# 12_Raspbbery_CM3.net
KiCad netlist of a schematic drawn in Altium Designer
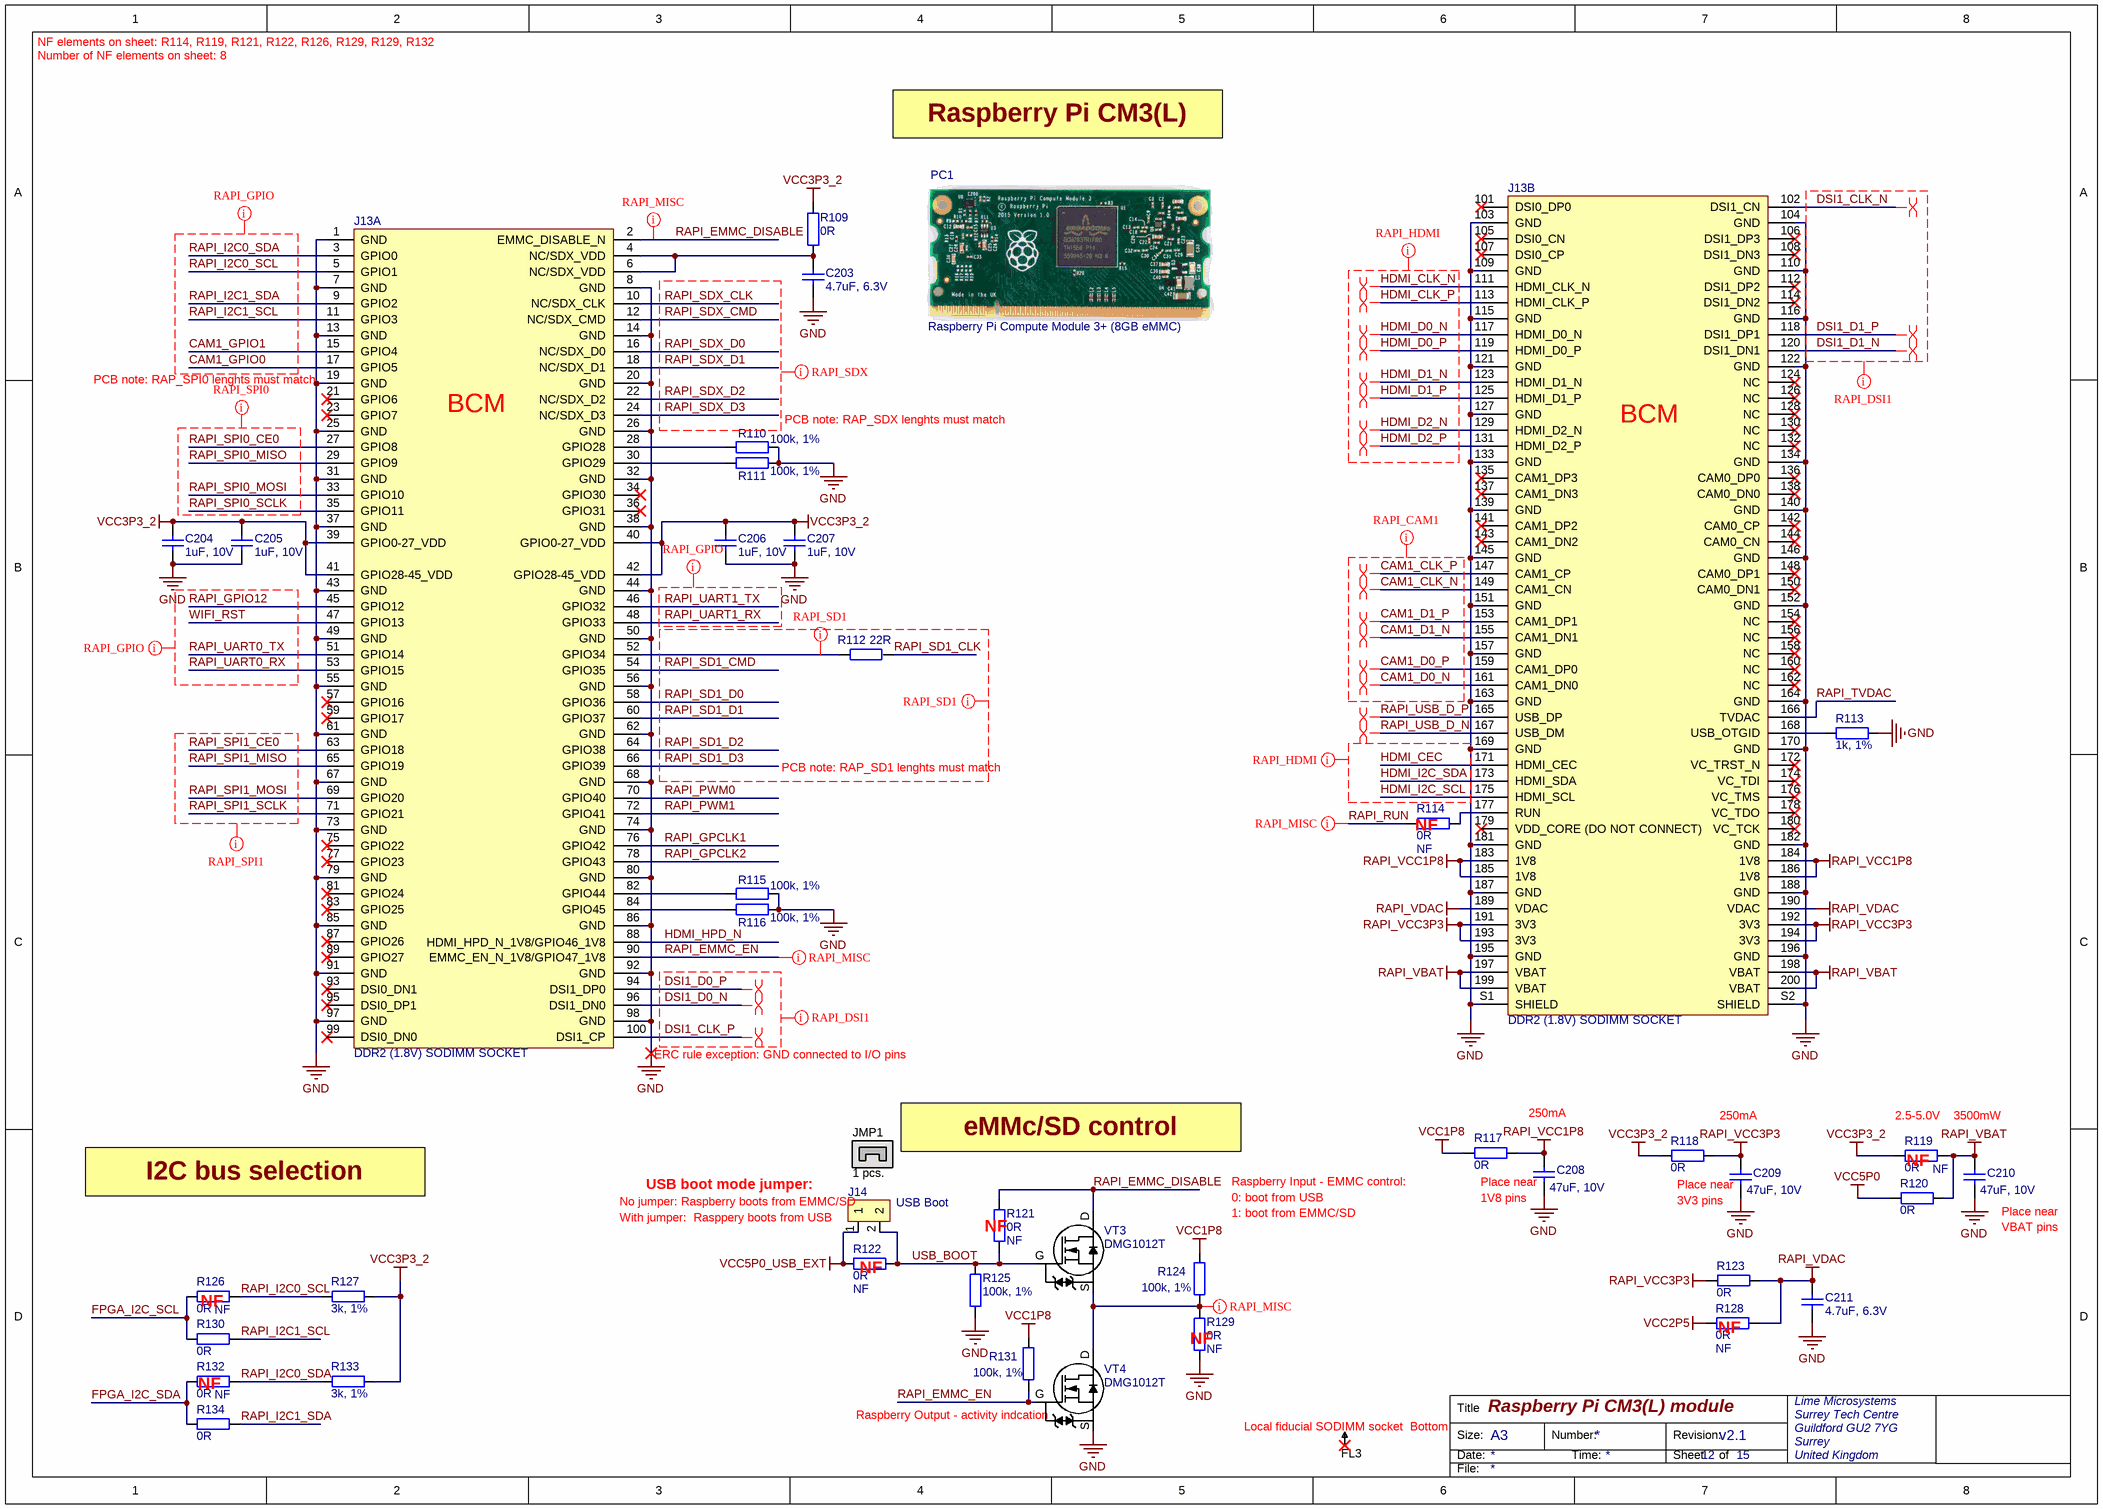
[diagram p0: 12_Raspbbery CM3.SchDoc]

(export (version "E")
  (design (tool "Eeschema 10.0.6"))
  (components
    (comp (ref "C203")
      (value "4.7uF, 6.3V")
      (footprint "CAP0402")
      (fields
        (field (name "MANUFACTURER") "Murata Electronics North America")
        (field (name "TOLERANCE") "±20%")
      )
      (libsource (lib "LimeMicroAltiumLib_schLib") (part "Cap_0402"))
    )
    (comp (ref "C204")
      (value "1uF, 10V")
      (footprint "CAP0402")
      (description "CAP CER 1UF 10V X5R 0402")
      (fields (field (name "MANUFACTURER") "Yageo") (field (name "TOLERANCE") "±20%"))
      (libsource (lib "LimeMicroAltiumLib_schLib") (part "Cap_0402"))
    )
    (comp (ref "C205")
      (value "1uF, 10V")
      (footprint "CAP0402")
      (description "CAP CER 1UF 10V X5R 0402")
      (fields (field (name "MANUFACTURER") "Yageo") (field (name "TOLERANCE") "±20%"))
      (libsource (lib "LimeMicroAltiumLib_schLib") (part "Cap_0402"))
    )
    (comp (ref "C206")
      (value "1uF, 10V")
      (footprint "CAP0402")
      (description "CAP CER 1UF 10V X5R 0402")
      (fields (field (name "MANUFACTURER") "Yageo") (field (name "TOLERANCE") "±20%"))
      (libsource (lib "LimeMicroAltiumLib_schLib") (part "Cap_0402"))
    )
    (comp (ref "C207")
      (value "1uF, 10V")
      (footprint "CAP0402")
      (description "CAP CER 1UF 10V X5R 0402")
      (fields (field (name "MANUFACTURER") "Yageo") (field (name "TOLERANCE") "±20%"))
      (libsource (lib "LimeMicroAltiumLib_schLib") (part "Cap_0402"))
    )
    (comp (ref "C208")
      (value "47uF, 10V")
      (footprint "CAP1206")
      (fields (field (name "TOLERANCE") "±20%") (field (name "MANUFACTURER") "TDK Corporation"))
      (libsource (lib "LimeFPGAboard_schLib") (part "Cap_1206"))
    )
    (comp (ref "C209")
      (value "47uF, 10V")
      (footprint "CAP1206")
      (fields (field (name "TOLERANCE") "±20%") (field (name "MANUFACTURER") "TDK Corporation"))
      (libsource (lib "LimeFPGAboard_schLib") (part "Cap_1206"))
    )
    (comp (ref "C210")
      (value "47uF, 10V")
      (footprint "CAP1206")
      (fields (field (name "TOLERANCE") "±20%") (field (name "MANUFACTURER") "TDK Corporation"))
      (libsource (lib "LimeFPGAboard_schLib") (part "Cap_1206"))
    )
    (comp (ref "C211")
      (value "4.7uF, 6.3V")
      (footprint "CAP0402")
      (fields
        (field (name "MANUFACTURER") "Murata Electronics North America")
        (field (name "TOLERANCE") "±20%")
      )
      (libsource (lib "LimeMicroAltiumLib_schLib") (part "Cap_0402"))
    )
    (comp (ref "FL3")
      (value "Fiducial")
      (footprint "Fiducial_local")
      (libsource (lib "VGTU_Altium_lib") (part "Fiducial"))
    )
    (comp (ref "J13")
      (value "DDR2 (1.8V) SODIMM SOCKET")
      (footprint "TE_1717254-1_DDR_SODIMM")
      (fields (field (name "MANUFACTURER") "TE Connectivity AMP Connectors"))
      (libsource (lib "LimeNet-Micro_2v1-SDR") (part "1717254-1"))
    )
    (comp (ref "J14")
      (value "USB Boot")
      (footprint "HDR_1x2")
      (fields (field (name "MANUFACTURER") "3M"))
      (libsource (lib "LimeFPGAboard_schLib") (part "Jumper"))
    )
    (comp (ref "JMP1")
      (value "1 pcs.")
      (description "Shorting Jumper, 2-position, 1.27mm pitch")
      (fields (field (name "MANUFACTURER") "Sullins"))
      (libsource (lib "LimeMicroAltiumLib_schLib") (part "JUMP_2P_CONN_HEADER"))
    )
    (comp (ref "PC1")
      (value "Raspberry Pi Compute Module 3+ (8GB eMMC)")
      (fields (field (name "MANUFACTURER") "RASPBERRY-PI"))
      (libsource (lib "LimeMicroAltiumLib_schLib_r01") (part "Raspberry_RPI-COMPUTE3"))
    )
    (comp (ref "R109")
      (value "0R")
      (footprint "RES0402")
      (fields (field (name "MANUFACTURER") "Yageo") (field (name "TOLERANCE") "Jumper"))
      (libsource (lib "LimeFPGAboard_schLib") (part "Res_0402"))
    )
    (comp (ref "R110")
      (value "100k, 1%")
      (footprint "RES0402")
      (fields
        (field (name "MANUFACTURER") "Vishay Dale")
        (field (name "TOLERANCE") "±1%")
        (field (name "MANUFACTURER PART NUMBER") "CRCW0402100KFKEDC")
      )
      (libsource (lib "LimeMicroAltiumLib_schLib") (part "Res_0402"))
    )
    (comp (ref "R111")
      (value "100k, 1%")
      (footprint "RES0402")
      (fields
        (field (name "MANUFACTURER") "Vishay Dale")
        (field (name "TOLERANCE") "±1%")
        (field (name "MANUFACTURER PART NUMBER") "CRCW0402100KFKEDC")
      )
      (libsource (lib "LimeMicroAltiumLib_schLib") (part "Res_0402"))
    )
    (comp (ref "R112")
      (value "22R")
      (footprint "RES0402")
      (fields (field (name "TOLERANCE") "±1%") (field (name "MANUFACTURER") "Yageo"))
      (libsource (lib "LimeFPGAboard_schLib") (part "Res_0402"))
    )
    (comp (ref "R113")
      (value "1k, 1%")
      (footprint "RES0402")
      (fields (field (name "MANUFACTURER") "Stackpole Electronics Inc") (field (name "TOLERANCE") "±1%"))
      (libsource (lib "LimeMicroAltiumLib_schLib") (part "Res_0402"))
    )
    (comp (ref "R114")
      (value "0R")
      (footprint "RES0402")
      (fields
        (field (name "MANUFACTURER") "Yageo")
        (field (name "ASSEMBLY INFO") "NF")
        (field (name "TOLERANCE") "Jumper")
      )
      (libsource (lib "LimeFPGAboard_schLib") (part "Res_0402"))
    )
    (comp (ref "R115")
      (value "100k, 1%")
      (footprint "RES0402")
      (fields
        (field (name "MANUFACTURER") "Vishay Dale")
        (field (name "TOLERANCE") "±1%")
        (field (name "MANUFACTURER PART NUMBER") "CRCW0402100KFKEDC")
      )
      (libsource (lib "LimeMicroAltiumLib_schLib") (part "Res_0402"))
    )
    (comp (ref "R116")
      (value "100k, 1%")
      (footprint "RES0402")
      (fields
        (field (name "MANUFACTURER") "Vishay Dale")
        (field (name "TOLERANCE") "±1%")
        (field (name "MANUFACTURER PART NUMBER") "CRCW0402100KFKEDC")
      )
      (libsource (lib "LimeMicroAltiumLib_schLib") (part "Res_0402"))
    )
    (comp (ref "R117")
      (value "0R")
      (footprint "RES0805")
      (fields (field (name "MANUFACTURER") "Vishay Dale") (field (name "TOLERANCE") "Jumper"))
      (libsource (lib "LimeMicroAltiumLib_schLib") (part "Res_0402"))
    )
    (comp (ref "R118")
      (value "0R")
      (footprint "RES0805")
      (fields (field (name "MANUFACTURER") "Vishay Dale") (field (name "TOLERANCE") "Jumper"))
      (libsource (lib "LimeMicroAltiumLib_schLib") (part "Res_0402"))
    )
    (comp (ref "R119")
      (value "0R")
      (footprint "RES0805")
      (fields
        (field (name "ASSEMBLY INFO") "NF")
        (field (name "MANUFACTURER") "Vishay Dale")
        (field (name "TOLERANCE") "Jumper")
      )
      (libsource (lib "LimeMicroAltiumLib_schLib") (part "Res_0402"))
    )
    (comp (ref "R120")
      (value "0R")
      (footprint "RES0805")
      (fields (field (name "MANUFACTURER") "Vishay Dale") (field (name "TOLERANCE") "Jumper"))
      (libsource (lib "LimeMicroAltiumLib_schLib") (part "Res_0402"))
    )
    (comp (ref "R121")
      (value "0R")
      (footprint "RES0402")
      (fields
        (field (name "MANUFACTURER") "Yageo")
        (field (name "ASSEMBLY INFO") "NF")
        (field (name "TOLERANCE") "Jumper")
      )
      (libsource (lib "LimeFPGAboard_schLib") (part "Res_0402"))
    )
    (comp (ref "R122")
      (value "0R")
      (footprint "RES0402")
      (fields
        (field (name "ASSEMBLY INFO") "NF")
        (field (name "MANUFACTURER") "Yageo")
        (field (name "TOLERANCE") "Jumper")
      )
      (libsource (lib "LimeMicroAltiumLib_schLib") (part "Res_0402"))
    )
    (comp (ref "R123")
      (value "0R")
      (footprint "RES0402")
      (fields (field (name "MANUFACTURER") "Yageo") (field (name "TOLERANCE") "Jumper"))
      (libsource (lib "LimeFPGAboard_schLib") (part "Res_0402"))
    )
    (comp (ref "R124")
      (value "100k, 1%")
      (footprint "RES0402")
      (fields
        (field (name "MANUFACTURER") "Vishay Dale")
        (field (name "TOLERANCE") "±1%")
        (field (name "MANUFACTURER PART NUMBER") "CRCW0402100KFKEDC")
      )
      (libsource (lib "LimeMicroAltiumLib_schLib") (part "Res_0402"))
    )
    (comp (ref "R125")
      (value "100k, 1%")
      (footprint "RES0402")
      (fields
        (field (name "MANUFACTURER") "Vishay Dale")
        (field (name "TOLERANCE") "±1%")
        (field (name "MANUFACTURER PART NUMBER") "CRCW0402100KFKEDC")
      )
      (libsource (lib "LimeMicroAltiumLib_schLib") (part "Res_0402"))
    )
    (comp (ref "R126")
      (value "0R")
      (footprint "RES0402")
      (fields
        (field (name "MANUFACTURER") "Yageo")
        (field (name "ASSEMBLY INFO") "NF")
        (field (name "TOLERANCE") "Jumper")
      )
      (libsource (lib "LimeFPGAboard_schLib") (part "Res_0402"))
    )
    (comp (ref "R127")
      (value "3k, 1%")
      (footprint "RES0402")
      (fields (field (name "TOLERANCE") "±1%") (field (name "MANUFACTURER") "Vishay Dale"))
      (libsource (lib "LimeMicroAltiumLib_schLib") (part "Res_0402"))
    )
    (comp (ref "R128")
      (value "0R")
      (footprint "RES0402")
      (fields
        (field (name "MANUFACTURER") "Yageo")
        (field (name "ASSEMBLY INFO") "NF")
        (field (name "TOLERANCE") "Jumper")
      )
      (libsource (lib "LimeFPGAboard_schLib") (part "Res_0402"))
    )
    (comp (ref "R129")
      (value "0R")
      (footprint "RES0402")
      (fields
        (field (name "MANUFACTURER") "Yageo")
        (field (name "ASSEMBLY INFO") "NF")
        (field (name "TOLERANCE") "Jumper")
      )
      (libsource (lib "LimeFPGAboard_schLib") (part "Res_0402"))
    )
    (comp (ref "R130")
      (value "0R")
      (footprint "RES0402")
      (fields (field (name "MANUFACTURER") "Yageo") (field (name "TOLERANCE") "Jumper"))
      (libsource (lib "LimeFPGAboard_schLib") (part "Res_0402"))
    )
    (comp (ref "R131")
      (value "100k, 1%")
      (footprint "RES0402")
      (fields
        (field (name "MANUFACTURER") "Vishay Dale")
        (field (name "TOLERANCE") "±1%")
        (field (name "MANUFACTURER PART NUMBER") "CRCW0402100KFKEDC")
      )
      (libsource (lib "LimeMicroAltiumLib_schLib") (part "Res_0402"))
    )
    (comp (ref "R132")
      (value "0R")
      (footprint "RES0402")
      (fields
        (field (name "MANUFACTURER") "Yageo")
        (field (name "ASSEMBLY INFO") "NF")
        (field (name "TOLERANCE") "Jumper")
      )
      (libsource (lib "LimeFPGAboard_schLib") (part "Res_0402"))
    )
    (comp (ref "R133")
      (value "3k, 1%")
      (footprint "RES0402")
      (fields (field (name "TOLERANCE") "±1%") (field (name "MANUFACTURER") "Vishay Dale"))
      (libsource (lib "LimeMicroAltiumLib_schLib") (part "Res_0402"))
    )
    (comp (ref "R134")
      (value "0R")
      (footprint "RES0402")
      (fields (field (name "MANUFACTURER") "Yageo") (field (name "TOLERANCE") "Jumper"))
      (libsource (lib "LimeFPGAboard_schLib") (part "Res_0402"))
    )
    (comp (ref "VT3")
      (value "DMG1012T")
      (footprint "SOT523")
      (fields (field (name "MANUFACTURER") "Diodes Incorporated"))
      (libsource (lib "LimeNet-Micro_2v1-SDR") (part "DMG1012T"))
    )
    (comp (ref "VT4")
      (value "DMG1012T")
      (footprint "SOT523")
      (fields (field (name "MANUFACTURER") "Diodes Incorporated"))
      (libsource (lib "LimeNet-Micro_2v1-SDR") (part "DMG1012T"))
    )
  )
  (nets
    (net (code "1") (name "/CAM1_CLK_N") (class "Default")
      (node (ref "J13") (pin "149") (pinfunction "CAM1_CN_149") (pintype "passive"))
    )
    (net (code "2") (name "/CAM1_CLK_P") (class "Default")
      (node (ref "J13") (pin "147") (pinfunction "CAM1_CP_147") (pintype "passive"))
    )
    (net (code "3") (name "/CAM1_D0_N") (class "Default")
      (node (ref "J13") (pin "161") (pinfunction "CAM1_DN0_161") (pintype "passive"))
    )
    (net (code "4") (name "/CAM1_D0_P") (class "Default")
      (node (ref "J13") (pin "159") (pinfunction "CAM1_DP0_159") (pintype "passive"))
    )
    (net (code "5") (name "/CAM1_D1_N") (class "Default")
      (node (ref "J13") (pin "155") (pinfunction "CAM1_DN1_155") (pintype "passive"))
    )
    (net (code "6") (name "/CAM1_D1_P") (class "Default")
      (node (ref "J13") (pin "153") (pinfunction "CAM1_DP1_153") (pintype "passive"))
    )
    (net (code "7") (name "/CAM1_GPIO0") (class "Default")
      (node (ref "J13") (pin "17") (pinfunction "GPIO5_17") (pintype "passive"))
    )
    (net (code "8") (name "/CAM1_GPIO1") (class "Default")
      (node (ref "J13") (pin "15") (pinfunction "GPIO4_15") (pintype "passive"))
    )
    (net (code "9") (name "/DSI1_CLK_N") (class "Default")
      (node (ref "J13") (pin "102") (pinfunction "DSI1_CN_102") (pintype "passive"))
    )
    (net (code "10") (name "/DSI1_CLK_P") (class "Default")
      (node (ref "J13") (pin "100") (pinfunction "DSI1_CP_100") (pintype "passive"))
    )
    (net (code "11") (name "/DSI1_D0_N") (class "Default")
      (node (ref "J13") (pin "96") (pinfunction "DSI1_DN0_96") (pintype "passive"))
    )
    (net (code "12") (name "/DSI1_D0_P") (class "Default")
      (node (ref "J13") (pin "94") (pinfunction "DSI1_DP0_94") (pintype "passive"))
    )
    (net (code "13") (name "/DSI1_D1_N") (class "Default")
      (node (ref "J13") (pin "120") (pinfunction "DSI1_DN1_120") (pintype "passive"))
    )
    (net (code "14") (name "/DSI1_D1_P") (class "Default")
      (node (ref "J13") (pin "118") (pinfunction "DSI1_DP1_118") (pintype "passive"))
    )
    (net (code "15") (name "/FPGA_I2C_SCL") (class "Default")
      (node (ref "R126") (pin "1") (pinfunction "1_1") (pintype "passive"))
      (node (ref "R130") (pin "1") (pinfunction "1_1") (pintype "passive"))
    )
    (net (code "16") (name "/FPGA_I2C_SDA") (class "Default")
      (node (ref "R132") (pin "1") (pinfunction "1_1") (pintype "passive"))
      (node (ref "R134") (pin "1") (pinfunction "1_1") (pintype "passive"))
    )
    (net (code "17") (name "/HDMI_CEC") (class "Default")
      (node (ref "J13") (pin "171") (pinfunction "HDMI_CEC_171") (pintype "passive"))
    )
    (net (code "18") (name "/HDMI_CLK_N") (class "Default")
      (node (ref "J13") (pin "111") (pinfunction "HDMI_CLK_N_111") (pintype "passive"))
    )
    (net (code "19") (name "/HDMI_CLK_P") (class "Default")
      (node (ref "J13") (pin "113") (pinfunction "HDMI_CLK_P_113") (pintype "passive"))
    )
    (net (code "20") (name "/HDMI_D0_N") (class "Default")
      (node (ref "J13") (pin "117") (pinfunction "HDMI_D0_N_117") (pintype "passive"))
    )
    (net (code "21") (name "/HDMI_D0_P") (class "Default")
      (node (ref "J13") (pin "119") (pinfunction "HDMI_D0_P_119") (pintype "passive"))
    )
    (net (code "22") (name "/HDMI_D1_N") (class "Default")
      (node (ref "J13") (pin "123") (pinfunction "HDMI_D1_N_123") (pintype "passive"))
    )
    (net (code "23") (name "/HDMI_D1_P") (class "Default")
      (node (ref "J13") (pin "125") (pinfunction "HDMI_D1_P_125") (pintype "passive"))
    )
    (net (code "24") (name "/HDMI_D2_N") (class "Default")
      (node (ref "J13") (pin "129") (pinfunction "HDMI_D2_N_129") (pintype "passive"))
    )
    (net (code "25") (name "/HDMI_D2_P") (class "Default")
      (node (ref "J13") (pin "131") (pinfunction "HDMI_D2_P_131") (pintype "passive"))
    )
    (net (code "26") (name "/HDMI_HPD_N") (class "Default")
      (node (ref "J13") (pin "88") (pinfunction "HDMI_HPD_N_1V8/GPIO46_1V8_88") (pintype "passive"))
    )
    (net (code "27") (name "/HDMI_I2C_SCL") (class "Default")
      (node (ref "J13") (pin "175") (pinfunction "HDMI_SCL_175") (pintype "passive"))
    )
    (net (code "28") (name "/HDMI_I2C_SDA") (class "Default")
      (node (ref "J13") (pin "173") (pinfunction "HDMI_SDA_173") (pintype "passive"))
    )
    (net (code "29") (name "/RAPI_EMMC_DISABLE") (class "Default")
      (node (ref "J13") (pin "2") (pinfunction "EMMC_DISABLE_N_2") (pintype "passive"))
      (node (ref "R121") (pin "1") (pinfunction "1_1") (pintype "passive"))
      (node (ref "VT3") (pin "D") (pinfunction "D_D") (pintype "passive"))
    )
    (net (code "30") (name "/RAPI_EMMC_EN") (class "Default")
      (node (ref "J13") (pin "90") (pinfunction "EMMC_EN_N_1V8/GPIO47_1V8_90") (pintype "passive"))
      (node (ref "R131") (pin "2") (pinfunction "2_2") (pintype "passive"))
      (node (ref "VT4") (pin "G") (pinfunction "G_G") (pintype "passive"))
    )
    (net (code "31") (name "/RAPI_GPCLK1") (class "Default")
      (node (ref "J13") (pin "76") (pinfunction "GPIO42_76") (pintype "passive"))
    )
    (net (code "32") (name "/RAPI_GPCLK2") (class "Default")
      (node (ref "J13") (pin "78") (pinfunction "GPIO43_78") (pintype "passive"))
    )
    (net (code "33") (name "/RAPI_GPIO12") (class "Default")
      (node (ref "J13") (pin "45") (pinfunction "GPIO12_45") (pintype "passive"))
    )
    (net (code "34") (name "/RAPI_I2C0_SCL") (class "Default")
      (node (ref "J13") (pin "5") (pinfunction "GPIO1_5") (pintype "passive"))
      (node (ref "R126") (pin "2") (pinfunction "2_2") (pintype "passive"))
      (node (ref "R127") (pin "2") (pinfunction "2_2") (pintype "passive"))
    )
    (net (code "35") (name "/RAPI_I2C0_SDA") (class "Default")
      (node (ref "J13") (pin "3") (pinfunction "GPIO0_3") (pintype "passive"))
      (node (ref "R132") (pin "2") (pinfunction "2_2") (pintype "passive"))
      (node (ref "R133") (pin "2") (pinfunction "2_2") (pintype "passive"))
    )
    (net (code "36") (name "/RAPI_I2C1_SCL") (class "Default")
      (node (ref "J13") (pin "11") (pinfunction "GPIO3_11") (pintype "passive"))
      (node (ref "R130") (pin "2") (pinfunction "2_2") (pintype "passive"))
    )
    (net (code "37") (name "/RAPI_I2C1_SDA") (class "Default")
      (node (ref "J13") (pin "9") (pinfunction "GPIO2_9") (pintype "passive"))
      (node (ref "R134") (pin "2") (pinfunction "2_2") (pintype "passive"))
    )
    (net (code "38") (name "/RAPI_PWM0") (class "Default")
      (node (ref "J13") (pin "70") (pinfunction "GPIO40_70") (pintype "passive"))
    )
    (net (code "39") (name "/RAPI_PWM1") (class "Default")
      (node (ref "J13") (pin "72") (pinfunction "GPIO41_72") (pintype "passive"))
    )
    (net (code "40") (name "/RAPI_RUN") (class "Default")
      (node (ref "R114") (pin "2") (pinfunction "2_2") (pintype "passive"))
    )
    (net (code "41") (name "/RAPI_SD1_CLK") (class "Default")
      (node (ref "R112") (pin "2") (pinfunction "2_2") (pintype "passive"))
    )
    (net (code "42") (name "/RAPI_SD1_CMD") (class "Default")
      (node (ref "J13") (pin "54") (pinfunction "GPIO35_54") (pintype "passive"))
    )
    (net (code "43") (name "/RAPI_SD1_D0") (class "Default")
      (node (ref "J13") (pin "58") (pinfunction "GPIO36_58") (pintype "passive"))
    )
    (net (code "44") (name "/RAPI_SD1_D1") (class "Default")
      (node (ref "J13") (pin "60") (pinfunction "GPIO37_60") (pintype "passive"))
    )
    (net (code "45") (name "/RAPI_SD1_D2") (class "Default")
      (node (ref "J13") (pin "64") (pinfunction "GPIO38_64") (pintype "passive"))
    )
    (net (code "46") (name "/RAPI_SD1_D3") (class "Default")
      (node (ref "J13") (pin "66") (pinfunction "GPIO39_66") (pintype "passive"))
    )
    (net (code "47") (name "/RAPI_SDX_CLK") (class "Default")
      (node (ref "J13") (pin "10") (pinfunction "NC/SDX_CLK_10") (pintype "passive"))
    )
    (net (code "48") (name "/RAPI_SDX_CMD") (class "Default")
      (node (ref "J13") (pin "12") (pinfunction "NC/SDX_CMD_12") (pintype "passive"))
    )
    (net (code "49") (name "/RAPI_SDX_D0") (class "Default")
      (node (ref "J13") (pin "16") (pinfunction "NC/SDX_D0_16") (pintype "passive"))
    )
    (net (code "50") (name "/RAPI_SDX_D1") (class "Default")
      (node (ref "J13") (pin "18") (pinfunction "NC/SDX_D1_18") (pintype "passive"))
    )
    (net (code "51") (name "/RAPI_SDX_D2") (class "Default")
      (node (ref "J13") (pin "22") (pinfunction "NC/SDX_D2_22") (pintype "passive"))
    )
    (net (code "52") (name "/RAPI_SDX_D3") (class "Default")
      (node (ref "J13") (pin "24") (pinfunction "NC/SDX_D3_24") (pintype "passive"))
    )
    (net (code "53") (name "/RAPI_SPI0_CE0") (class "Default")
      (node (ref "J13") (pin "27") (pinfunction "GPIO8_27") (pintype "passive"))
    )
    (net (code "54") (name "/RAPI_SPI0_MISO") (class "Default")
      (node (ref "J13") (pin "29") (pinfunction "GPIO9_29") (pintype "passive"))
    )
    (net (code "55") (name "/RAPI_SPI0_MOSI") (class "Default")
      (node (ref "J13") (pin "33") (pinfunction "GPIO10_33") (pintype "passive"))
    )
    (net (code "56") (name "/RAPI_SPI0_SCLK") (class "Default")
      (node (ref "J13") (pin "35") (pinfunction "GPIO11_35") (pintype "passive"))
    )
    (net (code "57") (name "/RAPI_SPI1_CE0") (class "Default")
      (node (ref "J13") (pin "63") (pinfunction "GPIO18_63") (pintype "passive"))
    )
    (net (code "58") (name "/RAPI_SPI1_MISO") (class "Default")
      (node (ref "J13") (pin "65") (pinfunction "GPIO19_65") (pintype "passive"))
    )
    (net (code "59") (name "/RAPI_SPI1_MOSI") (class "Default")
      (node (ref "J13") (pin "69") (pinfunction "GPIO20_69") (pintype "passive"))
    )
    (net (code "60") (name "/RAPI_SPI1_SCLK") (class "Default")
      (node (ref "J13") (pin "71") (pinfunction "GPIO21_71") (pintype "passive"))
    )
    (net (code "61") (name "/RAPI_TVDAC") (class "Default")
      (node (ref "J13") (pin "166") (pinfunction "TVDAC_166") (pintype "passive"))
    )
    (net (code "62") (name "/RAPI_UART0_RX") (class "Default")
      (node (ref "J13") (pin "53") (pinfunction "GPIO15_53") (pintype "passive"))
    )
    (net (code "63") (name "/RAPI_UART0_TX") (class "Default")
      (node (ref "J13") (pin "51") (pinfunction "GPIO14_51") (pintype "passive"))
    )
    (net (code "64") (name "/RAPI_UART1_RX") (class "Default")
      (node (ref "J13") (pin "48") (pinfunction "GPIO33_48") (pintype "passive"))
    )
    (net (code "65") (name "/RAPI_UART1_TX") (class "Default")
      (node (ref "J13") (pin "46") (pinfunction "GPIO32_46") (pintype "passive"))
    )
    (net (code "66") (name "/RAPI_USB_D_N") (class "Default")
      (node (ref "J13") (pin "167") (pinfunction "USB_DM_167") (pintype "passive"))
    )
    (net (code "67") (name "/RAPI_USB_D_P") (class "Default")
      (node (ref "J13") (pin "165") (pinfunction "USB_DP_165") (pintype "passive"))
    )
    (net (code "68") (name "/USB_BOOT") (class "Default")
      (node (ref "J14") (pin "2") (pinfunction "2_2") (pintype "passive"))
      (node (ref "R121") (pin "2") (pinfunction "2_2") (pintype "passive"))
      (node (ref "R122") (pin "2") (pinfunction "2_2") (pintype "passive"))
      (node (ref "R125") (pin "1") (pinfunction "1_1") (pintype "passive"))
      (node (ref "VT3") (pin "G") (pinfunction "G_G") (pintype "passive"))
    )
    (net (code "69") (name "/WIFI_RST") (class "Default")
      (node (ref "J13") (pin "47") (pinfunction "GPIO13_47") (pintype "passive"))
    )
    (net (code "70") (name "GND") (class "Default")
      (node (ref "C203") (pin "2") (pinfunction "2_2") (pintype "passive"))
      (node (ref "C204") (pin "1") (pinfunction "1_1") (pintype "passive"))
      (node (ref "C205") (pin "1") (pinfunction "1_1") (pintype "passive"))
      (node (ref "C206") (pin "1") (pinfunction "1_1") (pintype "passive"))
      (node (ref "C207") (pin "1") (pinfunction "1_1") (pintype "passive"))
      (node (ref "C208") (pin "1") (pinfunction "1_1") (pintype "passive"))
      (node (ref "C209") (pin "1") (pinfunction "1_1") (pintype "passive"))
      (node (ref "C210") (pin "1") (pinfunction "1_1") (pintype "passive"))
      (node (ref "C211") (pin "1") (pinfunction "1_1") (pintype "passive"))
      (node (ref "J13") (pin "1") (pinfunction "GND_1") (pintype "passive"))
      (node (ref "J13") (pin "103") (pinfunction "GND_103") (pintype "passive"))
      (node (ref "J13") (pin "104") (pinfunction "GND_104") (pintype "passive"))
      (node (ref "J13") (pin "109") (pinfunction "GND_109") (pintype "passive"))
      (node (ref "J13") (pin "110") (pinfunction "GND_110") (pintype "passive"))
      (node (ref "J13") (pin "115") (pinfunction "GND_115") (pintype "passive"))
      (node (ref "J13") (pin "116") (pinfunction "GND_116") (pintype "passive"))
      (node (ref "J13") (pin "121") (pinfunction "GND_121") (pintype "passive"))
      (node (ref "J13") (pin "122") (pinfunction "GND_122") (pintype "passive"))
      (node (ref "J13") (pin "127") (pinfunction "GND_127") (pintype "passive"))
      (node (ref "J13") (pin "13") (pinfunction "GND_13") (pintype "passive"))
      (node (ref "J13") (pin "133") (pinfunction "GND_133") (pintype "passive"))
      (node (ref "J13") (pin "134") (pinfunction "GND_134") (pintype "passive"))
      (node (ref "J13") (pin "139") (pinfunction "GND_139") (pintype "passive"))
      (node (ref "J13") (pin "14") (pinfunction "GND_14") (pintype "passive"))
      (node (ref "J13") (pin "140") (pinfunction "GND_140") (pintype "passive"))
      (node (ref "J13") (pin "145") (pinfunction "GND_145") (pintype "passive"))
      (node (ref "J13") (pin "146") (pinfunction "GND_146") (pintype "passive"))
      (node (ref "J13") (pin "151") (pinfunction "GND_151") (pintype "passive"))
      (node (ref "J13") (pin "152") (pinfunction "GND_152") (pintype "passive"))
      (node (ref "J13") (pin "157") (pinfunction "GND_157") (pintype "passive"))
      (node (ref "J13") (pin "163") (pinfunction "GND_163") (pintype "passive"))
      (node (ref "J13") (pin "164") (pinfunction "GND_164") (pintype "passive"))
      (node (ref "J13") (pin "169") (pinfunction "GND_169") (pintype "passive"))
      (node (ref "J13") (pin "170") (pinfunction "GND_170") (pintype "passive"))
      (node (ref "J13") (pin "181") (pinfunction "GND_181") (pintype "passive"))
      (node (ref "J13") (pin "182") (pinfunction "GND_182") (pintype "passive"))
      (node (ref "J13") (pin "187") (pinfunction "GND_187") (pintype "passive"))
      (node (ref "J13") (pin "188") (pinfunction "GND_188") (pintype "passive"))
      (node (ref "J13") (pin "19") (pinfunction "GND_19") (pintype "passive"))
      (node (ref "J13") (pin "195") (pinfunction "GND_195") (pintype "passive"))
      (node (ref "J13") (pin "196") (pinfunction "GND_196") (pintype "passive"))
      (node (ref "J13") (pin "20") (pinfunction "GND_20") (pintype "passive"))
      (node (ref "J13") (pin "25") (pinfunction "GND_25") (pintype "passive"))
      (node (ref "J13") (pin "26") (pinfunction "GND_26") (pintype "passive"))
      (node (ref "J13") (pin "31") (pinfunction "GND_31") (pintype "passive"))
      (node (ref "J13") (pin "32") (pinfunction "GND_32") (pintype "passive"))
      (node (ref "J13") (pin "37") (pinfunction "GND_37") (pintype "passive"))
      (node (ref "J13") (pin "38") (pinfunction "GND_38") (pintype "passive"))
      (node (ref "J13") (pin "43") (pinfunction "GND_43") (pintype "passive"))
      (node (ref "J13") (pin "44") (pinfunction "GND_44") (pintype "passive"))
      (node (ref "J13") (pin "49") (pinfunction "GND_49") (pintype "passive"))
      (node (ref "J13") (pin "50") (pinfunction "GND_50") (pintype "passive"))
      (node (ref "J13") (pin "55") (pinfunction "GND_55") (pintype "passive"))
      (node (ref "J13") (pin "56") (pinfunction "GND_56") (pintype "passive"))
      (node (ref "J13") (pin "61") (pinfunction "GND_61") (pintype "passive"))
      (node (ref "J13") (pin "62") (pinfunction "GND_62") (pintype "passive"))
      (node (ref "J13") (pin "67") (pinfunction "GND_67") (pintype "passive"))
      (node (ref "J13") (pin "68") (pinfunction "GND_68") (pintype "passive"))
      (node (ref "J13") (pin "7") (pinfunction "GND_7") (pintype "passive"))
      (node (ref "J13") (pin "73") (pinfunction "GND_73") (pintype "passive"))
      (node (ref "J13") (pin "74") (pinfunction "GND_74") (pintype "passive"))
      (node (ref "J13") (pin "79") (pinfunction "GND_79") (pintype "passive"))
      (node (ref "J13") (pin "8") (pinfunction "GND_8") (pintype "passive"))
      (node (ref "J13") (pin "80") (pinfunction "GND_80") (pintype "passive"))
      (node (ref "J13") (pin "85") (pinfunction "GND_85") (pintype "passive"))
      (node (ref "J13") (pin "86") (pinfunction "GND_86") (pintype "passive"))
      (node (ref "J13") (pin "91") (pinfunction "GND_91") (pintype "passive"))
      (node (ref "J13") (pin "92") (pinfunction "GND_92") (pintype "passive"))
      (node (ref "J13") (pin "97") (pinfunction "GND_97") (pintype "passive"))
      (node (ref "J13") (pin "98") (pinfunction "GND_98") (pintype "passive"))
      (node (ref "J13") (pin "S1") (pinfunction "SHIELD_S1") (pintype "passive"))
      (node (ref "J13") (pin "S2") (pinfunction "SHIELD_S2") (pintype "passive"))
      (node (ref "R110") (pin "1") (pinfunction "1_1") (pintype "passive"))
      (node (ref "R111") (pin "1") (pinfunction "1_1") (pintype "passive"))
      (node (ref "R113") (pin "1") (pinfunction "1_1") (pintype "passive"))
      (node (ref "R115") (pin "1") (pinfunction "1_1") (pintype "passive"))
      (node (ref "R116") (pin "1") (pinfunction "1_1") (pintype "passive"))
      (node (ref "R125") (pin "2") (pinfunction "2_2") (pintype "passive"))
      (node (ref "R129") (pin "1") (pinfunction "1_1") (pintype "passive"))
      (node (ref "VT4") (pin "S") (pinfunction "S_S") (pintype "passive"))
    )
    (net (code "71") (name "Net-(C203-Pad1)") (class "Default")
      (node (ref "C203") (pin "1") (pinfunction "1_1") (pintype "passive"))
      (node (ref "J13") (pin "4") (pinfunction "NC/SDX_VDD_4") (pintype "passive"))
      (node (ref "J13") (pin "6") (pinfunction "NC/SDX_VDD_6") (pintype "passive"))
      (node (ref "R109") (pin "1") (pinfunction "1_1") (pintype "passive"))
    )
    (net (code "72") (name "Net-(J13A-GPIO28)") (class "Default")
      (node (ref "J13") (pin "28") (pinfunction "GPIO28_28") (pintype "passive"))
      (node (ref "R110") (pin "2") (pinfunction "2_2") (pintype "passive"))
    )
    (net (code "73") (name "Net-(J13A-GPIO29)") (class "Default")
      (node (ref "J13") (pin "30") (pinfunction "GPIO29_30") (pintype "passive"))
      (node (ref "R111") (pin "2") (pinfunction "2_2") (pintype "passive"))
    )
    (net (code "74") (name "Net-(J13A-GPIO34)") (class "Default")
      (node (ref "J13") (pin "52") (pinfunction "GPIO34_52") (pintype "passive"))
      (node (ref "R112") (pin "1") (pinfunction "1_1") (pintype "passive"))
    )
    (net (code "75") (name "Net-(J13A-GPIO44)") (class "Default")
      (node (ref "J13") (pin "82") (pinfunction "GPIO44_82") (pintype "passive"))
      (node (ref "R115") (pin "2") (pinfunction "2_2") (pintype "passive"))
    )
    (net (code "76") (name "Net-(J13A-GPIO45)") (class "Default")
      (node (ref "J13") (pin "84") (pinfunction "GPIO45_84") (pintype "passive"))
      (node (ref "R116") (pin "2") (pinfunction "2_2") (pintype "passive"))
    )
    (net (code "77") (name "Net-(J13B-RUN)") (class "Default")
      (node (ref "J13") (pin "177") (pinfunction "RUN_177") (pintype "passive"))
      (node (ref "R114") (pin "1") (pinfunction "1_1") (pintype "passive"))
    )
    (net (code "78") (name "Net-(J13B-USB_OTGID)") (class "Default")
      (node (ref "J13") (pin "168") (pinfunction "USB_OTGID_168") (pintype "passive"))
      (node (ref "R113") (pin "2") (pinfunction "2_2") (pintype "passive"))
    )
    (net (code "79") (name "Net-(R124-Pad2)") (class "Default")
      (node (ref "R124") (pin "2") (pinfunction "2_2") (pintype "passive"))
      (node (ref "R129") (pin "2") (pinfunction "2_2") (pintype "passive"))
      (node (ref "VT3") (pin "S") (pinfunction "S_S") (pintype "passive"))
      (node (ref "VT4") (pin "D") (pinfunction "D_D") (pintype "passive"))
    )
    (net (code "80") (name "RAPI_VBAT") (class "Default")
      (node (ref "C210") (pin "2") (pinfunction "2_2") (pintype "passive"))
      (node (ref "J13") (pin "197") (pinfunction "VBAT_197") (pintype "passive"))
      (node (ref "J13") (pin "198") (pinfunction "VBAT_198") (pintype "passive"))
      (node (ref "J13") (pin "199") (pinfunction "VBAT_199") (pintype "passive"))
      (node (ref "J13") (pin "200") (pinfunction "VBAT_200") (pintype "passive"))
      (node (ref "R119") (pin "1") (pinfunction "1_1") (pintype "passive"))
      (node (ref "R120") (pin "1") (pinfunction "1_1") (pintype "passive"))
    )
    (net (code "81") (name "RAPI_VCC1P8") (class "Default")
      (node (ref "C208") (pin "2") (pinfunction "2_2") (pintype "passive"))
      (node (ref "J13") (pin "183") (pinfunction "1V8_183") (pintype "passive"))
      (node (ref "J13") (pin "184") (pinfunction "1V8_184") (pintype "passive"))
      (node (ref "J13") (pin "185") (pinfunction "1V8_185") (pintype "passive"))
      (node (ref "J13") (pin "186") (pinfunction "1V8_186") (pintype "passive"))
      (node (ref "R117") (pin "1") (pinfunction "1_1") (pintype "passive"))
    )
    (net (code "82") (name "RAPI_VCC3P3") (class "Default")
      (node (ref "C209") (pin "2") (pinfunction "2_2") (pintype "passive"))
      (node (ref "J13") (pin "191") (pinfunction "3V3_191") (pintype "passive"))
      (node (ref "J13") (pin "192") (pinfunction "3V3_192") (pintype "passive"))
      (node (ref "J13") (pin "193") (pinfunction "3V3_193") (pintype "passive"))
      (node (ref "J13") (pin "194") (pinfunction "3V3_194") (pintype "passive"))
      (node (ref "R118") (pin "1") (pinfunction "1_1") (pintype "passive"))
      (node (ref "R123") (pin "2") (pinfunction "2_2") (pintype "passive"))
    )
    (net (code "83") (name "RAPI_VDAC") (class "Default")
      (node (ref "C211") (pin "2") (pinfunction "2_2") (pintype "passive"))
      (node (ref "J13") (pin "189") (pinfunction "VDAC_189") (pintype "passive"))
      (node (ref "J13") (pin "190") (pinfunction "VDAC_190") (pintype "passive"))
      (node (ref "R123") (pin "1") (pinfunction "1_1") (pintype "passive"))
      (node (ref "R128") (pin "2") (pinfunction "2_2") (pintype "passive"))
    )
    (net (code "84") (name "VCC1P8") (class "Default")
      (node (ref "R117") (pin "2") (pinfunction "2_2") (pintype "passive"))
      (node (ref "R124") (pin "1") (pinfunction "1_1") (pintype "passive"))
      (node (ref "R131") (pin "1") (pinfunction "1_1") (pintype "passive"))
    )
    (net (code "85") (name "VCC2P5") (class "Default")
      (node (ref "R128") (pin "1") (pinfunction "1_1") (pintype "passive"))
    )
    (net (code "86") (name "VCC3P3_2") (class "Default")
      (node (ref "C204") (pin "2") (pinfunction "2_2") (pintype "passive"))
      (node (ref "C205") (pin "2") (pinfunction "2_2") (pintype "passive"))
      (node (ref "C206") (pin "2") (pinfunction "2_2") (pintype "passive"))
      (node (ref "C207") (pin "2") (pinfunction "2_2") (pintype "passive"))
      (node (ref "J13") (pin "39") (pinfunction "GPIO0-27_VDD_39") (pintype "passive"))
      (node (ref "J13") (pin "40") (pinfunction "GPIO0-27_VDD_40") (pintype "passive"))
      (node (ref "J13") (pin "41") (pinfunction "GPIO28-45_VDD_41") (pintype "passive"))
      (node (ref "J13") (pin "42") (pinfunction "GPIO28-45_VDD_42") (pintype "passive"))
      (node (ref "R109") (pin "2") (pinfunction "2_2") (pintype "passive"))
      (node (ref "R118") (pin "2") (pinfunction "2_2") (pintype "passive"))
      (node (ref "R119") (pin "2") (pinfunction "2_2") (pintype "passive"))
      (node (ref "R127") (pin "1") (pinfunction "1_1") (pintype "passive"))
      (node (ref "R133") (pin "1") (pinfunction "1_1") (pintype "passive"))
    )
    (net (code "87") (name "VCC5P0") (class "Default")
      (node (ref "R120") (pin "2") (pinfunction "2_2") (pintype "passive"))
    )
    (net (code "88") (name "VCC5P0_USB_EXT") (class "Default")
      (node (ref "J14") (pin "1") (pinfunction "1_1") (pintype "passive"))
      (node (ref "R122") (pin "1") (pinfunction "1_1") (pintype "passive"))
    )
    (net (code "89") (name "unconnected-(FL3-Pad1)") (class "Default")
      (node (ref "FL3") (pin "1") (pintype "passive+no_connect"))
    )
    (net (code "90") (name "unconnected-(J13A-DSI0_DN0-Pad99)") (class "Default")
      (node (ref "J13") (pin "99") (pinfunction "DSI0_DN0_99") (pintype "passive+no_connect"))
    )
    (net (code "91") (name "unconnected-(J13A-DSI0_DN1-Pad93)") (class "Default")
      (node (ref "J13") (pin "93") (pinfunction "DSI0_DN1_93") (pintype "passive+no_connect"))
    )
    (net (code "92") (name "unconnected-(J13A-DSI0_DP1-Pad95)") (class "Default")
      (node (ref "J13") (pin "95") (pinfunction "DSI0_DP1_95") (pintype "passive+no_connect"))
    )
    (net (code "93") (name "unconnected-(J13A-GPIO6-Pad21)") (class "Default")
      (node (ref "J13") (pin "21") (pinfunction "GPIO6_21") (pintype "passive+no_connect"))
    )
    (net (code "94") (name "unconnected-(J13A-GPIO7-Pad23)") (class "Default")
      (node (ref "J13") (pin "23") (pinfunction "GPIO7_23") (pintype "passive+no_connect"))
    )
    (net (code "95") (name "unconnected-(J13A-GPIO16-Pad57)") (class "Default")
      (node (ref "J13") (pin "57") (pinfunction "GPIO16_57") (pintype "passive+no_connect"))
    )
    (net (code "96") (name "unconnected-(J13A-GPIO17-Pad59)") (class "Default")
      (node (ref "J13") (pin "59") (pinfunction "GPIO17_59") (pintype "passive+no_connect"))
    )
    (net (code "97") (name "unconnected-(J13A-GPIO22-Pad75)") (class "Default")
      (node (ref "J13") (pin "75") (pinfunction "GPIO22_75") (pintype "passive+no_connect"))
    )
    (net (code "98") (name "unconnected-(J13A-GPIO23-Pad77)") (class "Default")
      (node (ref "J13") (pin "77") (pinfunction "GPIO23_77") (pintype "passive+no_connect"))
    )
    (net (code "99") (name "unconnected-(J13A-GPIO24-Pad81)") (class "Default")
      (node (ref "J13") (pin "81") (pinfunction "GPIO24_81") (pintype "passive+no_connect"))
    )
    (net (code "100") (name "unconnected-(J13A-GPIO25-Pad83)") (class "Default")
      (node (ref "J13") (pin "83") (pinfunction "GPIO25_83") (pintype "passive+no_connect"))
    )
    (net (code "101") (name "unconnected-(J13A-GPIO26-Pad87)") (class "Default")
      (node (ref "J13") (pin "87") (pinfunction "GPIO26_87") (pintype "passive+no_connect"))
    )
    (net (code "102") (name "unconnected-(J13A-GPIO27-Pad89)") (class "Default")
      (node (ref "J13") (pin "89") (pinfunction "GPIO27_89") (pintype "passive+no_connect"))
    )
    (net (code "103") (name "unconnected-(J13A-GPIO30-Pad34)") (class "Default")
      (node (ref "J13") (pin "34") (pinfunction "GPIO30_34") (pintype "passive+no_connect"))
    )
    (net (code "104") (name "unconnected-(J13A-GPIO31-Pad36)") (class "Default")
      (node (ref "J13") (pin "36") (pinfunction "GPIO31_36") (pintype "passive+no_connect"))
    )
    (net (code "105") (name "unconnected-(J13B-CAM0_CN-Pad144)") (class "Default")
      (node (ref "J13") (pin "144") (pinfunction "CAM0_CN_144") (pintype "passive+no_connect"))
    )
    (net (code "106") (name "unconnected-(J13B-CAM0_CP-Pad142)") (class "Default")
      (node (ref "J13") (pin "142") (pinfunction "CAM0_CP_142") (pintype "passive+no_connect"))
    )
    (net (code "107") (name "unconnected-(J13B-CAM0_DN0-Pad138)") (class "Default")
      (node (ref "J13") (pin "138") (pinfunction "CAM0_DN0_138") (pintype "passive+no_connect"))
    )
    (net (code "108") (name "unconnected-(J13B-CAM0_DN1-Pad150)") (class "Default")
      (node (ref "J13") (pin "150") (pinfunction "CAM0_DN1_150") (pintype "passive+no_connect"))
    )
    (net (code "109") (name "unconnected-(J13B-CAM0_DP0-Pad136)") (class "Default")
      (node (ref "J13") (pin "136") (pinfunction "CAM0_DP0_136") (pintype "passive+no_connect"))
    )
    (net (code "110") (name "unconnected-(J13B-CAM0_DP1-Pad148)") (class "Default")
      (node (ref "J13") (pin "148") (pinfunction "CAM0_DP1_148") (pintype "passive+no_connect"))
    )
    (net (code "111") (name "unconnected-(J13B-CAM1_DN2-Pad143)") (class "Default")
      (node (ref "J13") (pin "143") (pinfunction "CAM1_DN2_143") (pintype "passive+no_connect"))
    )
    (net (code "112") (name "unconnected-(J13B-CAM1_DN3-Pad137)") (class "Default")
      (node (ref "J13") (pin "137") (pinfunction "CAM1_DN3_137") (pintype "passive+no_connect"))
    )
    (net (code "113") (name "unconnected-(J13B-CAM1_DP2-Pad141)") (class "Default")
      (node (ref "J13") (pin "141") (pinfunction "CAM1_DP2_141") (pintype "passive+no_connect"))
    )
    (net (code "114") (name "unconnected-(J13B-CAM1_DP3-Pad135)") (class "Default")
      (node (ref "J13") (pin "135") (pinfunction "CAM1_DP3_135") (pintype "passive+no_connect"))
    )
    (net (code "115") (name "unconnected-(J13B-DSI0_CN-Pad105)") (class "Default")
      (node (ref "J13") (pin "105") (pinfunction "DSI0_CN_105") (pintype "passive+no_connect"))
    )
    (net (code "116") (name "unconnected-(J13B-DSI0_CP-Pad107)") (class "Default")
      (node (ref "J13") (pin "107") (pinfunction "DSI0_CP_107") (pintype "passive+no_connect"))
    )
    (net (code "117") (name "unconnected-(J13B-DSI0_DP0-Pad101)") (class "Default")
      (node (ref "J13") (pin "101") (pinfunction "DSI0_DP0_101") (pintype "passive+no_connect"))
    )
    (net (code "118") (name "unconnected-(J13B-DSI1_DN2-Pad114)") (class "Default")
      (node (ref "J13") (pin "114") (pinfunction "DSI1_DN2_114") (pintype "passive+no_connect"))
    )
    (net (code "119") (name "unconnected-(J13B-DSI1_DN3-Pad108)") (class "Default")
      (node (ref "J13") (pin "108") (pinfunction "DSI1_DN3_108") (pintype "passive+no_connect"))
    )
    (net (code "120") (name "unconnected-(J13B-DSI1_DP2-Pad112)") (class "Default")
      (node (ref "J13") (pin "112") (pinfunction "DSI1_DP2_112") (pintype "passive+no_connect"))
    )
    (net (code "121") (name "unconnected-(J13B-DSI1_DP3-Pad106)") (class "Default")
      (node (ref "J13") (pin "106") (pinfunction "DSI1_DP3_106") (pintype "passive+no_connect"))
    )
    (net (code "122") (name "unconnected-(J13B-NC-Pad124)") (class "Default")
      (node (ref "J13") (pin "124") (pinfunction "NC_124") (pintype "passive+no_connect"))
    )
    (net (code "123") (name "unconnected-(J13B-NC-Pad126)") (class "Default")
      (node (ref "J13") (pin "126") (pinfunction "NC_126") (pintype "passive+no_connect"))
    )
    (net (code "124") (name "unconnected-(J13B-NC-Pad128)") (class "Default")
      (node (ref "J13") (pin "128") (pinfunction "NC_128") (pintype "passive+no_connect"))
    )
    (net (code "125") (name "unconnected-(J13B-NC-Pad130)") (class "Default")
      (node (ref "J13") (pin "130") (pinfunction "NC_130") (pintype "passive+no_connect"))
    )
    (net (code "126") (name "unconnected-(J13B-NC-Pad132)") (class "Default")
      (node (ref "J13") (pin "132") (pinfunction "NC_132") (pintype "passive+no_connect"))
    )
    (net (code "127") (name "unconnected-(J13B-NC-Pad154)") (class "Default")
      (node (ref "J13") (pin "154") (pinfunction "NC_154") (pintype "passive+no_connect"))
    )
    (net (code "128") (name "unconnected-(J13B-NC-Pad156)") (class "Default")
      (node (ref "J13") (pin "156") (pinfunction "NC_156") (pintype "passive+no_connect"))
    )
    (net (code "129") (name "unconnected-(J13B-NC-Pad158)") (class "Default")
      (node (ref "J13") (pin "158") (pinfunction "NC_158") (pintype "passive+no_connect"))
    )
    (net (code "130") (name "unconnected-(J13B-NC-Pad160)") (class "Default")
      (node (ref "J13") (pin "160") (pinfunction "NC_160") (pintype "passive+no_connect"))
    )
    (net (code "131") (name "unconnected-(J13B-NC-Pad162)") (class "Default")
      (node (ref "J13") (pin "162") (pinfunction "NC_162") (pintype "passive+no_connect"))
    )
    (net (code "132") (name "unconnected-(J13B-VC_TCK-Pad180)") (class "Default")
      (node (ref "J13") (pin "180") (pinfunction "VC_TCK_180") (pintype "passive+no_connect"))
    )
    (net (code "133") (name "unconnected-(J13B-VC_TDI-Pad174)") (class "Default")
      (node (ref "J13") (pin "174") (pinfunction "VC_TDI_174") (pintype "passive+no_connect"))
    )
    (net (code "134") (name "unconnected-(J13B-VC_TDO-Pad178)") (class "Default")
      (node (ref "J13") (pin "178") (pinfunction "VC_TDO_178") (pintype "passive+no_connect"))
    )
    (net (code "135") (name "unconnected-(J13B-VC_TMS-Pad176)") (class "Default")
      (node (ref "J13") (pin "176") (pinfunction "VC_TMS_176") (pintype "passive+no_connect"))
    )
    (net (code "136") (name "unconnected-(J13B-VC_TRST_N-Pad172)") (class "Default")
      (node (ref "J13") (pin "172") (pinfunction "VC_TRST_N_172") (pintype "passive+no_connect"))
    )
    (net (code "137") (name "unconnected-(J13B-VDD_CORE_(DO_NOT_CONNECT)-Pad179)") (class "Default")
      (node (ref "J13") (pin "179") (pinfunction "VDD_CORE_(DO_NOT_CONNECT)_179") (pintype "passive+no_connect"))
    )
    (net (code "138") (name "unconnected-(JMP1-Pad1)") (class "Default")
      (node (ref "JMP1") (pin "1") (pinfunction "1_1") (pintype "passive"))
    )
    (net (code "139") (name "unconnected-(JMP1-Pad2)") (class "Default")
      (node (ref "JMP1") (pin "2") (pinfunction "2_2") (pintype "passive"))
    )
  )
)
